# pcb.net
KiCad netlist of a schematic drawn in EAGLE
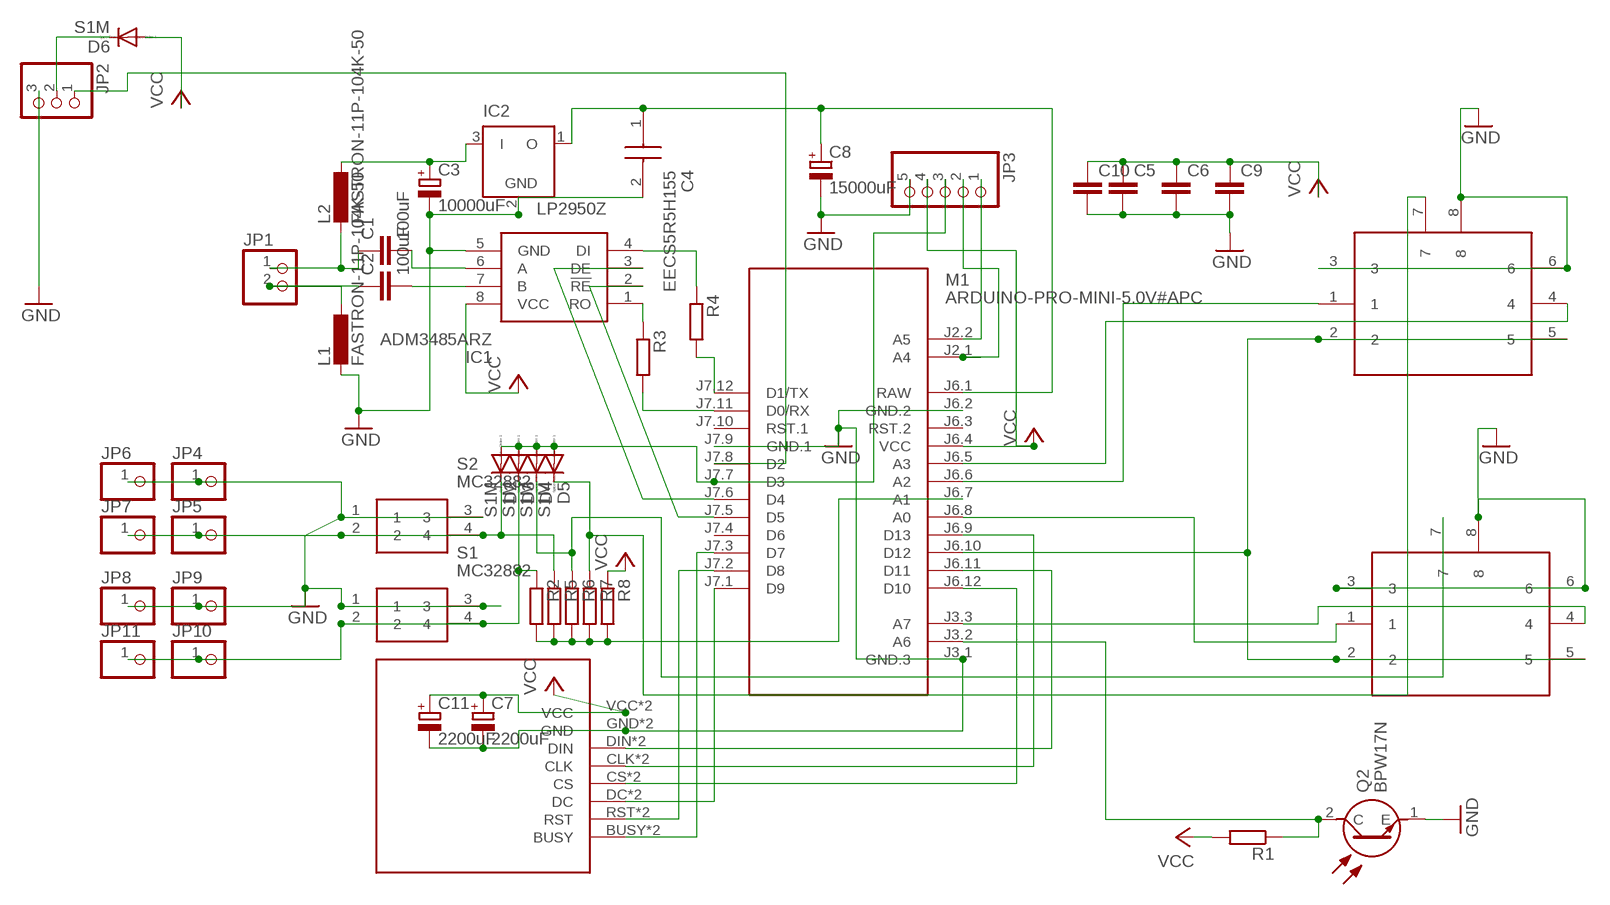
[diagram p0: schematic, sheet 1]

(export (version "E")
  (design (tool "Eeschema 10.0.6"))
  (components
    (comp (ref "C1")
      (value "100uF")
      (footprint "eagle-import:C1210")
      (libsource (lib "eagle-import") (part "C-EUC1210"))
    )
    (comp (ref "C2")
      (value "100uF")
      (footprint "eagle-import:C1210")
      (libsource (lib "eagle-import") (part "C-EUC1210"))
    )
    (comp (ref "C3")
      (value "10000uF")
      (footprint "eagle-import:E7,5-18")
      (libsource (lib "eagle-import") (part "CPOL-EUE7.5-18"))
    )
    (comp (ref "C4")
      (value "EECS5R5H155")
      (footprint "eagle-import:SG(H)")
      (fields (field (name "RS_PART_NUMBER") "9190657"))
      (libsource (lib "eagle-import") (part "EECS5R5H155"))
    )
    (comp (ref "C5")
      (value "C-EUC1812")
      (footprint "eagle-import:C1812")
      (libsource (lib "eagle-import") (part "C-EUC1812"))
    )
    (comp (ref "C6")
      (value "C-EUC1812")
      (footprint "eagle-import:C1812")
      (libsource (lib "eagle-import") (part "C-EUC1812"))
    )
    (comp (ref "C7")
      (value "2200uF")
      (footprint "eagle-import:TT5D9")
      (libsource (lib "eagle-import") (part "CPOL-EUTT5D9"))
    )
    (comp (ref "C8")
      (value "15000uF")
      (footprint "eagle-import:E7,5-18")
      (libsource (lib "eagle-import") (part "CPOL-EUE7.5-18"))
    )
    (comp (ref "C9")
      (value "C-EUC1812")
      (footprint "eagle-import:C1812")
      (libsource (lib "eagle-import") (part "C-EUC1812"))
    )
    (comp (ref "C10")
      (value "C-EUC1812")
      (footprint "eagle-import:C1812")
      (libsource (lib "eagle-import") (part "C-EUC1812"))
    )
    (comp (ref "C11")
      (value "2200uF")
      (footprint "eagle-import:TT5D9")
      (libsource (lib "eagle-import") (part "CPOL-EUTT5D9"))
    )
    (comp (ref "D2")
      (value "S1M")
      (footprint "eagle-import:SMA")
      (libsource (lib "eagle-import") (part "S1M"))
    )
    (comp (ref "D3")
      (value "S1M")
      (footprint "eagle-import:SMA")
      (libsource (lib "eagle-import") (part "S1M"))
    )
    (comp (ref "D4")
      (value "S1M")
      (footprint "eagle-import:SMA")
      (libsource (lib "eagle-import") (part "S1M"))
    )
    (comp (ref "D5")
      (value "S1M")
      (footprint "eagle-import:SMA")
      (libsource (lib "eagle-import") (part "S1M"))
    )
    (comp (ref "D6")
      (value "S1M")
      (footprint "eagle-import:SMA")
      (libsource (lib "eagle-import") (part "S1M"))
    )
    (comp (ref "IC1")
      (value "ADM3485ARZ")
      (footprint "eagle-import:SOIC127P600X175-8N")
      (fields (field (name "MOUSER_PART_NUMBER") "584-ADM3485ARZ") (field (name "RS_PART_NUMBER") "6977653P"))
      (libsource (lib "eagle-import") (part "ADM3485ARZ"))
    )
    (comp (ref "IC2")
      (value "LP2950Z")
      (footprint "eagle-import:TO92")
      (libsource (lib "eagle-import") (part "LP2950Z"))
    )
    (comp (ref "JP1")
      (value "PINHD-1X2")
      (footprint "eagle-import:1X02")
      (libsource (lib "eagle-import") (part "PINHD-1X2"))
    )
    (comp (ref "JP2")
      (value "PINHD-1X3")
      (footprint "eagle-import:1X03")
      (libsource (lib "eagle-import") (part "PINHD-1X3"))
    )
    (comp (ref "JP3")
      (value "PINHD-1X55X2MM")
      (footprint "eagle-import:1_05X2MM")
      (libsource (lib "eagle-import") (part "PINHD-1X55X2MM"))
    )
    (comp (ref "JP4")
      (value "PINHD-1X1")
      (footprint "eagle-import:1X01")
      (libsource (lib "eagle-import") (part "PINHD-1X1"))
    )
    (comp (ref "JP5")
      (value "PINHD-1X1")
      (footprint "eagle-import:1X01")
      (libsource (lib "eagle-import") (part "PINHD-1X1"))
    )
    (comp (ref "JP6")
      (value "PINHD-1X1")
      (footprint "eagle-import:1X01")
      (libsource (lib "eagle-import") (part "PINHD-1X1"))
    )
    (comp (ref "JP7")
      (value "PINHD-1X1")
      (footprint "eagle-import:1X01")
      (libsource (lib "eagle-import") (part "PINHD-1X1"))
    )
    (comp (ref "JP8")
      (value "PINHD-1X1")
      (footprint "eagle-import:1X01")
      (libsource (lib "eagle-import") (part "PINHD-1X1"))
    )
    (comp (ref "JP9")
      (value "PINHD-1X1")
      (footprint "eagle-import:1X01")
      (libsource (lib "eagle-import") (part "PINHD-1X1"))
    )
    (comp (ref "JP10")
      (value "PINHD-1X1")
      (footprint "eagle-import:1X01")
      (libsource (lib "eagle-import") (part "PINHD-1X1"))
    )
    (comp (ref "JP11")
      (value "PINHD-1X1")
      (footprint "eagle-import:1X01")
      (libsource (lib "eagle-import") (part "PINHD-1X1"))
    )
    (comp (ref "L1")
      (value "FASTRON-11P-104K-50")
      (footprint "eagle-import:E5-10,5")
      (libsource (lib "eagle-import") (part "FASTRON-11P-104K-50"))
    )
    (comp (ref "L2")
      (value "FASTRON-11P-104K-50")
      (footprint "eagle-import:E5-10,5")
      (libsource (lib "eagle-import") (part "FASTRON-11P-104K-50"))
    )
    (comp (ref "M1")
      (value "ARDUINO-PRO-MINI-5.0V#APC")
      (footprint "eagle-import:ARDUINO-PRO-MINI#APC")
      (libsource (lib "eagle-import") (part "ARDUINO-PRO-MINI-#APC5.0V"))
    )
    (comp (ref "Q2")
      (value "BPW17N")
      (footprint "eagle-import:BPW17N")
      (fields (field (name "MOUSER_PART_NUMBER") "782-BPW17N"))
      (libsource (lib "eagle-import") (part "BPW17N"))
    )
    (comp (ref "R1")
      (value "R-EU_R1206")
      (footprint "eagle-import:R1206")
      (libsource (lib "eagle-import") (part "R-EU_R1206"))
    )
    (comp (ref "R2")
      (value "R-EU_R1206")
      (footprint "eagle-import:R1206")
      (libsource (lib "eagle-import") (part "R-EU_R1206"))
    )
    (comp (ref "R3")
      (value "R-EU_R1206")
      (footprint "eagle-import:R1206")
      (libsource (lib "eagle-import") (part "R-EU_R1206"))
    )
    (comp (ref "R4")
      (value "R-EU_R1206")
      (footprint "eagle-import:R1206")
      (libsource (lib "eagle-import") (part "R-EU_R1206"))
    )
    (comp (ref "R5")
      (value "R-EU_R1206")
      (footprint "eagle-import:R1206")
      (libsource (lib "eagle-import") (part "R-EU_R1206"))
    )
    (comp (ref "R6")
      (value "R-EU_R1206")
      (footprint "eagle-import:R1206")
      (libsource (lib "eagle-import") (part "R-EU_R1206"))
    )
    (comp (ref "R7")
      (value "R-EU_R1206")
      (footprint "eagle-import:R1206")
      (libsource (lib "eagle-import") (part "R-EU_R1206"))
    )
    (comp (ref "R8")
      (value "R-EU_R1206")
      (footprint "eagle-import:R1206")
      (libsource (lib "eagle-import") (part "R-EU_R1206"))
    )
    (comp (ref "S1")
      (value "MC32882")
      (footprint "eagle-import:MC32882")
      (libsource (lib "eagle-import") (part "MC32882"))
    )
    (comp (ref "S2")
      (value "MC32882")
      (footprint "eagle-import:MC32882")
      (libsource (lib "eagle-import") (part "MC32882"))
    )
    (comp (ref "U$1")
      (value "FJ08K-S")
      (footprint "eagle-import:FJ08K-S")
      (libsource (lib "eagle-import") (part "FJ08K-S"))
    )
    (comp (ref "U$2")
      (value "FJ08K-S")
      (footprint "eagle-import:FJ08K-S")
      (libsource (lib "eagle-import") (part "FJ08K-S"))
    )
    (comp (ref "U$3")
      (value "1,54-E-PAPER")
      (footprint "eagle-import:1,54-E-PAPER")
      (libsource (lib "eagle-import") (part "1,54-E-PAPER"))
    )
  )
  (nets
    (net (code "1") (name "GND") (class "Default")
      (node (ref "C10") (pin "2") (pinfunction "2_2") (pintype "passive"))
      (node (ref "C11") (pin "-") (pinfunction "-_-") (pintype "passive"))
      (node (ref "C3") (pin "-") (pinfunction "-_-") (pintype "passive"))
      (node (ref "C4") (pin "2") (pinfunction "2_2") (pintype "bidirectional"))
      (node (ref "C5") (pin "2") (pinfunction "2_2") (pintype "passive"))
      (node (ref "C6") (pin "2") (pinfunction "2_2") (pintype "passive"))
      (node (ref "C7") (pin "-") (pinfunction "-_-") (pintype "passive"))
      (node (ref "C8") (pin "-") (pinfunction "-_-") (pintype "passive"))
      (node (ref "C9") (pin "2") (pinfunction "2_2") (pintype "passive"))
      (node (ref "IC1") (pin "5") (pinfunction "GND_5") (pintype "power_in"))
      (node (ref "IC2") (pin "2") (pinfunction "GND_2") (pintype "power_in"))
      (node (ref "JP2") (pin "3") (pinfunction "3_3") (pintype "passive"))
      (node (ref "JP3") (pin "5") (pinfunction "5_5") (pintype "passive"))
      (node (ref "JP4") (pin "1") (pinfunction "1_1") (pintype "passive"))
      (node (ref "JP6") (pin "1") (pinfunction "1_1") (pintype "passive"))
      (node (ref "JP8") (pin "1") (pinfunction "1_1") (pintype "passive"))
      (node (ref "JP9") (pin "1") (pinfunction "1_1") (pintype "passive"))
      (node (ref "L1") (pin "-") (pinfunction "2_-") (pintype "passive"))
      (node (ref "M1") (pin "J3.1") (pinfunction "GND.3_J3.1") (pintype "bidirectional"))
      (node (ref "M1") (pin "J6.2") (pinfunction "GND.2_J6.2") (pintype "power_in"))
      (node (ref "M1") (pin "J7.9") (pinfunction "GND.1_J7.9") (pintype "power_in"))
      (node (ref "Q2") (pin "1") (pinfunction "E_1") (pintype "bidirectional"))
      (node (ref "S1") (pin "1") (pinfunction "1_1") (pintype "bidirectional"))
      (node (ref "S1") (pin "3") (pinfunction "3_3") (pintype "bidirectional"))
      (node (ref "S2") (pin "1") (pinfunction "1_1") (pintype "bidirectional"))
      (node (ref "S2") (pin "3") (pinfunction "3_3") (pintype "bidirectional"))
      (node (ref "U$1") (pin "3") (pinfunction "3_3") (pintype "passive"))
      (node (ref "U$1") (pin "6") (pinfunction "6_6") (pintype "passive"))
      (node (ref "U$1") (pin "8") (pinfunction "8_8") (pintype "bidirectional"))
      (node (ref "U$2") (pin "3") (pinfunction "3_3") (pintype "passive"))
      (node (ref "U$2") (pin "6") (pinfunction "6_6") (pintype "passive"))
      (node (ref "U$2") (pin "8") (pinfunction "8_8") (pintype "bidirectional"))
      (node (ref "U$3") (pin "GND") (pinfunction "GND_GND") (pintype "bidirectional"))
      (node (ref "U$3") (pin "GND1") (pinfunction "GND_GND1") (pintype "bidirectional"))
    )
    (net (code "2") (name "Net-(D2-PadC)") (class "Default")
      (node (ref "D2") (pin "C") (pinfunction "C_C") (pintype "passive"))
      (node (ref "JP5") (pin "1") (pinfunction "1_1") (pintype "passive"))
      (node (ref "JP7") (pin "1") (pinfunction "1_1") (pintype "passive"))
      (node (ref "R5") (pin "1") (pinfunction "1_1") (pintype "passive"))
      (node (ref "S2") (pin "2") (pinfunction "2_2") (pintype "bidirectional"))
      (node (ref "S2") (pin "4") (pinfunction "4_4") (pintype "bidirectional"))
    )
    (net (code "3") (name "Net-(D3-PadC)") (class "Default")
      (node (ref "D3") (pin "C") (pinfunction "C_C") (pintype "passive"))
      (node (ref "JP10") (pin "1") (pinfunction "1_1") (pintype "passive"))
      (node (ref "JP11") (pin "1") (pinfunction "1_1") (pintype "passive"))
      (node (ref "R2") (pin "1") (pinfunction "1_1") (pintype "passive"))
      (node (ref "S1") (pin "2") (pinfunction "2_2") (pintype "bidirectional"))
      (node (ref "S1") (pin "4") (pinfunction "4_4") (pintype "bidirectional"))
    )
    (net (code "4") (name "Net-(D4-PadC)") (class "Default")
      (node (ref "D4") (pin "C") (pinfunction "C_C") (pintype "passive"))
      (node (ref "R6") (pin "1") (pinfunction "1_1") (pintype "passive"))
      (node (ref "U$2") (pin "7") (pinfunction "7_7") (pintype "bidirectional"))
    )
    (net (code "5") (name "Net-(D5-PadC)") (class "Default")
      (node (ref "D5") (pin "C") (pinfunction "C_C") (pintype "passive"))
      (node (ref "R7") (pin "1") (pinfunction "1_1") (pintype "passive"))
      (node (ref "U$1") (pin "7") (pinfunction "7_7") (pintype "bidirectional"))
    )
    (net (code "6") (name "Net-(D6-PadC)") (class "Default")
      (node (ref "D6") (pin "C") (pinfunction "C_C") (pintype "passive"))
      (node (ref "JP2") (pin "2") (pinfunction "2_2") (pintype "passive"))
    )
    (net (code "7") (name "Net-(IC1-A)") (class "Default")
      (node (ref "C1") (pin "2") (pinfunction "2_2") (pintype "passive"))
      (node (ref "IC1") (pin "6") (pinfunction "A_6") (pintype "bidirectional"))
    )
    (net (code "8") (name "Net-(IC1-B)") (class "Default")
      (node (ref "C2") (pin "2") (pinfunction "2_2") (pintype "passive"))
      (node (ref "IC1") (pin "7") (pinfunction "B_7") (pintype "bidirectional"))
    )
    (net (code "9") (name "Net-(IC1-DE)") (class "Default")
      (node (ref "IC1") (pin "3") (pinfunction "DE_3") (pintype "bidirectional"))
      (node (ref "M1") (pin "J7.6") (pinfunction "D4_J7.6") (pintype "bidirectional"))
    )
    (net (code "10") (name "Net-(IC1-DI)") (class "Default")
      (node (ref "IC1") (pin "4") (pinfunction "DI_4") (pintype "bidirectional"))
      (node (ref "R4") (pin "1") (pinfunction "1_1") (pintype "passive"))
    )
    (net (code "11") (name "Net-(IC1-RO)") (class "Default")
      (node (ref "IC1") (pin "1") (pinfunction "RO_1") (pintype "bidirectional"))
      (node (ref "R3") (pin "1") (pinfunction "1_1") (pintype "passive"))
    )
    (net (code "12") (name "Net-(IC1-~{RE})") (class "Default")
      (node (ref "IC1") (pin "2") (pinfunction "~{RE}_2") (pintype "bidirectional"))
      (node (ref "M1") (pin "J7.5") (pinfunction "D5_J7.5") (pintype "bidirectional"))
    )
    (net (code "13") (name "Net-(IC2-I)") (class "Default")
      (node (ref "C3") (pin "+") (pinfunction "+_+") (pintype "passive"))
      (node (ref "IC2") (pin "3") (pinfunction "I_3") (pintype "input"))
      (node (ref "L2") (pin "+") (pinfunction "1_+") (pintype "passive"))
    )
    (net (code "14") (name "Net-(IC2-O)") (class "Default")
      (node (ref "C4") (pin "1") (pinfunction "1_1") (pintype "bidirectional"))
      (node (ref "C8") (pin "+") (pinfunction "+_+") (pintype "passive"))
      (node (ref "IC2") (pin "1") (pinfunction "O_1") (pintype "input"))
      (node (ref "M1") (pin "J6.1") (pinfunction "RAW_J6.1") (pintype "power_in"))
    )
    (net (code "15") (name "Net-(L1-1)") (class "Default")
      (node (ref "C2") (pin "1") (pinfunction "1_1") (pintype "passive"))
      (node (ref "JP1") (pin "2") (pinfunction "2_2") (pintype "passive"))
      (node (ref "L1") (pin "+") (pinfunction "1_+") (pintype "passive"))
    )
    (net (code "16") (name "Net-(L2-2)") (class "Default")
      (node (ref "C1") (pin "1") (pinfunction "1_1") (pintype "passive"))
      (node (ref "JP1") (pin "1") (pinfunction "1_1") (pintype "passive"))
      (node (ref "L2") (pin "-") (pinfunction "2_-") (pintype "passive"))
    )
    (net (code "17") (name "Net-(M1-A0)") (class "Default")
      (node (ref "M1") (pin "J6.8") (pinfunction "A0_J6.8") (pintype "bidirectional"))
      (node (ref "U$2") (pin "1") (pinfunction "1_1") (pintype "passive"))
    )
    (net (code "18") (name "Net-(M1-A1)") (class "Default")
      (node (ref "M1") (pin "J6.7") (pinfunction "A1_J6.7") (pintype "bidirectional"))
      (node (ref "R2") (pin "2") (pinfunction "2_2") (pintype "passive"))
      (node (ref "R5") (pin "2") (pinfunction "2_2") (pintype "passive"))
      (node (ref "R6") (pin "2") (pinfunction "2_2") (pintype "passive"))
      (node (ref "R7") (pin "2") (pinfunction "2_2") (pintype "passive"))
      (node (ref "R8") (pin "2") (pinfunction "2_2") (pintype "passive"))
    )
    (net (code "19") (name "Net-(M1-A2)") (class "Default")
      (node (ref "M1") (pin "J6.6") (pinfunction "A2_J6.6") (pintype "bidirectional"))
      (node (ref "U$1") (pin "1") (pinfunction "1_1") (pintype "passive"))
    )
    (net (code "20") (name "Net-(M1-A3)") (class "Default")
      (node (ref "M1") (pin "J6.5") (pinfunction "A3_J6.5") (pintype "bidirectional"))
      (node (ref "U$1") (pin "4") (pinfunction "4_4") (pintype "passive"))
    )
    (net (code "21") (name "Net-(M1-A4)") (class "Default")
      (node (ref "JP3") (pin "2") (pinfunction "2_2") (pintype "passive"))
      (node (ref "M1") (pin "J2.1") (pinfunction "A4_J2.1") (pintype "bidirectional"))
    )
    (net (code "22") (name "Net-(M1-A5)") (class "Default")
      (node (ref "JP3") (pin "1") (pinfunction "1_1") (pintype "passive"))
      (node (ref "M1") (pin "J2.2") (pinfunction "A5_J2.2") (pintype "bidirectional"))
    )
    (net (code "23") (name "Net-(M1-A6)") (class "Default")
      (node (ref "M1") (pin "J3.2") (pinfunction "A6_J3.2") (pintype "bidirectional"))
      (node (ref "Q2") (pin "2") (pinfunction "C_2") (pintype "bidirectional"))
      (node (ref "R1") (pin "1") (pinfunction "1_1") (pintype "passive"))
    )
    (net (code "24") (name "Net-(M1-A7)") (class "Default")
      (node (ref "M1") (pin "J3.3") (pinfunction "A7_J3.3") (pintype "bidirectional"))
      (node (ref "U$2") (pin "4") (pinfunction "4_4") (pintype "passive"))
    )
    (net (code "25") (name "Net-(M1-D0{slash}RX)") (class "Default")
      (node (ref "M1") (pin "J7.11") (pinfunction "D0/RX_J7.11") (pintype "bidirectional"))
      (node (ref "R3") (pin "2") (pinfunction "2_2") (pintype "passive"))
    )
    (net (code "26") (name "Net-(M1-D1{slash}TX)") (class "Default")
      (node (ref "M1") (pin "J7.12") (pinfunction "D1/TX_J7.12") (pintype "bidirectional"))
      (node (ref "R4") (pin "2") (pinfunction "2_2") (pintype "passive"))
    )
    (net (code "27") (name "Net-(M1-D2)") (class "Default")
      (node (ref "JP2") (pin "1") (pinfunction "1_1") (pintype "passive"))
      (node (ref "M1") (pin "J7.8") (pinfunction "D2_J7.8") (pintype "bidirectional"))
    )
    (net (code "28") (name "Net-(M1-D3)") (class "Default")
      (node (ref "D2") (pin "A") (pinfunction "A_A") (pintype "passive"))
      (node (ref "D3") (pin "A") (pinfunction "A_A") (pintype "passive"))
      (node (ref "D4") (pin "A") (pinfunction "A_A") (pintype "passive"))
      (node (ref "D5") (pin "A") (pinfunction "A_A") (pintype "passive"))
      (node (ref "JP3") (pin "3") (pinfunction "3_3") (pintype "passive"))
      (node (ref "M1") (pin "J7.7") (pinfunction "D3_J7.7") (pintype "bidirectional"))
    )
    (net (code "29") (name "Net-(M1-D7)") (class "Default")
      (node (ref "M1") (pin "J7.3") (pinfunction "D7_J7.3") (pintype "bidirectional"))
      (node (ref "U$3") (pin "BUSY") (pinfunction "BUSY_BUSY") (pintype "bidirectional"))
      (node (ref "U$3") (pin "BUSY1") (pinfunction "BUSY_BUSY1") (pintype "bidirectional"))
    )
    (net (code "30") (name "Net-(M1-D8)") (class "Default")
      (node (ref "M1") (pin "J7.2") (pinfunction "D8_J7.2") (pintype "bidirectional"))
      (node (ref "U$3") (pin "RST") (pinfunction "RST_RST") (pintype "bidirectional"))
      (node (ref "U$3") (pin "RST1") (pinfunction "RST_RST1") (pintype "bidirectional"))
    )
    (net (code "31") (name "Net-(M1-D9)") (class "Default")
      (node (ref "M1") (pin "J7.1") (pinfunction "D9_J7.1") (pintype "bidirectional"))
      (node (ref "U$3") (pin "DC") (pinfunction "DC_DC") (pintype "bidirectional"))
      (node (ref "U$3") (pin "DC1") (pinfunction "DC_DC1") (pintype "bidirectional"))
    )
    (net (code "32") (name "Net-(M1-D10)") (class "Default")
      (node (ref "M1") (pin "J6.12") (pinfunction "D10_J6.12") (pintype "bidirectional"))
      (node (ref "U$3") (pin "CS") (pinfunction "CS_CS") (pintype "bidirectional"))
      (node (ref "U$3") (pin "CS1") (pinfunction "CS_CS1") (pintype "bidirectional"))
    )
    (net (code "33") (name "Net-(M1-D11)") (class "Default")
      (node (ref "M1") (pin "J6.11") (pinfunction "D11_J6.11") (pintype "bidirectional"))
      (node (ref "U$3") (pin "DIN") (pinfunction "DIN_DIN") (pintype "bidirectional"))
      (node (ref "U$3") (pin "DIN1") (pinfunction "DIN_DIN1") (pintype "bidirectional"))
    )
    (net (code "34") (name "Net-(M1-D12)") (class "Default")
      (node (ref "M1") (pin "J6.10") (pinfunction "D12_J6.10") (pintype "bidirectional"))
      (node (ref "U$1") (pin "2") (pinfunction "2_2") (pintype "passive"))
      (node (ref "U$1") (pin "5") (pinfunction "5_5") (pintype "passive"))
      (node (ref "U$2") (pin "2") (pinfunction "2_2") (pintype "passive"))
      (node (ref "U$2") (pin "5") (pinfunction "5_5") (pintype "passive"))
    )
    (net (code "35") (name "Net-(M1-D13)") (class "Default")
      (node (ref "M1") (pin "J6.9") (pinfunction "D13_J6.9") (pintype "bidirectional"))
      (node (ref "U$3") (pin "CLK") (pinfunction "CLK_CLK") (pintype "bidirectional"))
      (node (ref "U$3") (pin "CLK1") (pinfunction "CLK_CLK1") (pintype "bidirectional"))
    )
    (net (code "36") (name "VCC") (class "Default")
      (node (ref "C10") (pin "1") (pinfunction "1_1") (pintype "passive"))
      (node (ref "C11") (pin "+") (pinfunction "+_+") (pintype "passive"))
      (node (ref "C5") (pin "1") (pinfunction "1_1") (pintype "passive"))
      (node (ref "C6") (pin "1") (pinfunction "1_1") (pintype "passive"))
      (node (ref "C7") (pin "+") (pinfunction "+_+") (pintype "passive"))
      (node (ref "C9") (pin "1") (pinfunction "1_1") (pintype "passive"))
      (node (ref "D6") (pin "A") (pinfunction "A_A") (pintype "passive"))
      (node (ref "IC1") (pin "8") (pinfunction "VCC_8") (pintype "power_in"))
      (node (ref "JP3") (pin "4") (pinfunction "4_4") (pintype "passive"))
      (node (ref "M1") (pin "J6.4") (pinfunction "VCC_J6.4") (pintype "power_in"))
      (node (ref "R1") (pin "2") (pinfunction "2_2") (pintype "passive"))
      (node (ref "R8") (pin "1") (pinfunction "1_1") (pintype "passive"))
      (node (ref "U$3") (pin "VCC") (pinfunction "VCC_VCC") (pintype "bidirectional"))
      (node (ref "U$3") (pin "VCC1") (pinfunction "VCC_VCC1") (pintype "bidirectional"))
    )
    (net (code "37") (name "unconnected-(M1-D6-PadJ7.4)") (class "Default")
      (node (ref "M1") (pin "J7.4") (pinfunction "D6_J7.4") (pintype "bidirectional"))
    )
    (net (code "38") (name "unconnected-(M1-RST.1-PadJ7.10)") (class "Default")
      (node (ref "M1") (pin "J7.10") (pinfunction "RST.1_J7.10") (pintype "bidirectional"))
    )
    (net (code "39") (name "unconnected-(M1-RST.2-PadJ6.3)") (class "Default")
      (node (ref "M1") (pin "J6.3") (pinfunction "RST.2_J6.3") (pintype "bidirectional"))
    )
  )
)
